# Remote.net
KiCad netlist of a schematic drawn in EAGLE
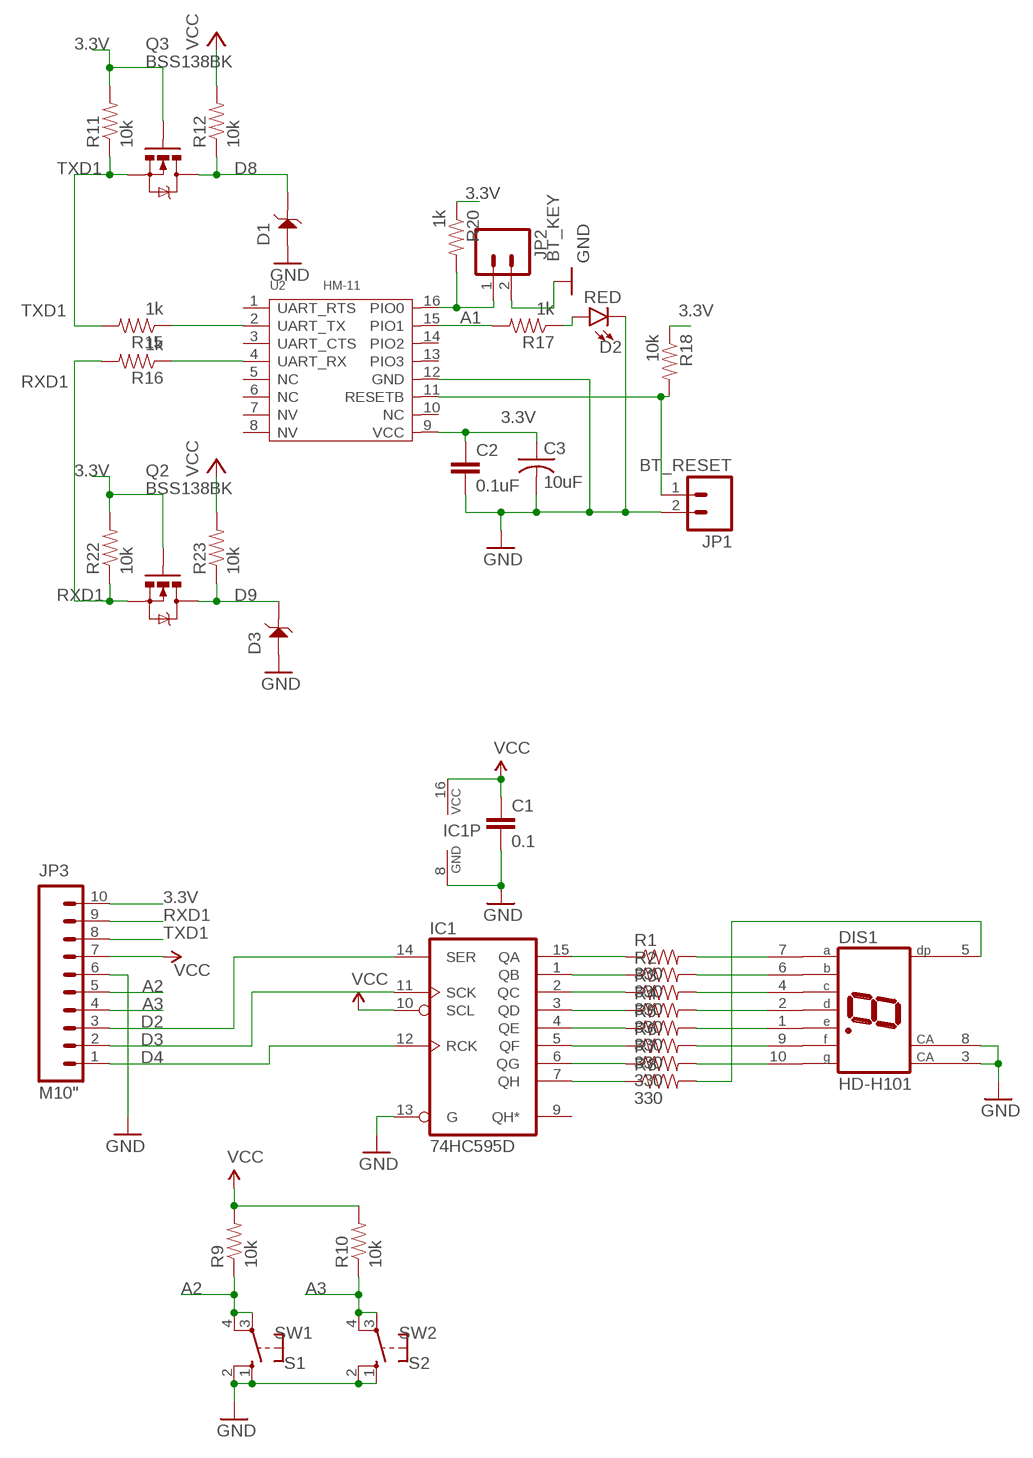
[diagram p0: schematic, sheet 1]

(export (version "E")
  (design (tool "Eeschema 10.0.6"))
  (components
    (comp (ref "C1")
      (value "0.1")
      (footprint "eagle-import:0805")
      (libsource (lib "eagle-import") (part "CAP0805"))
    )
    (comp (ref "C2")
      (value "0.1uF")
      (footprint "eagle-import:0805")
      (libsource (lib "eagle-import") (part "SparkFun-Capacitors_CAP0805"))
    )
    (comp (ref "C3")
      (value "10uF")
      (footprint "eagle-import:C1206")
      (libsource (lib "eagle-import") (part "C-USC1206"))
    )
    (comp (ref "D1")
      (value "SMF5.0A")
      (footprint "eagle-import:SOD123-2.7X1.6")
      (libsource (lib "eagle-import") (part "D-ESD-2P'CESD5V0D1'"))
    )
    (comp (ref "D2")
      (value "RED")
      (footprint "eagle-import:LED-0603")
      (libsource (lib "eagle-import") (part "LED-RED0603"))
    )
    (comp (ref "D3")
      (value "SMF5.0A")
      (footprint "eagle-import:SOD123-2.7X1.6")
      (libsource (lib "eagle-import") (part "D-ESD-2P'CESD5V0D1'"))
    )
    (comp (ref "DIS1")
      (value "HD-H101")
      (footprint "eagle-import:HDSP-M")
      (libsource (lib "eagle-import") (part "HD-H101"))
    )
    (comp (ref "IC1")
      (value "74HC595D")
      (footprint "eagle-import:SO16")
      (libsource (lib "eagle-import") (part "74595DHC"))
    )
    (comp (ref "JP1")
      (value "BT_RESET")
      (footprint "eagle-import:1X02")
      (libsource (lib "eagle-import") (part "M02PTH"))
    )
    (comp (ref "JP2")
      (value "BT_KEY")
      (footprint "eagle-import:1X02")
      (libsource (lib "eagle-import") (part "M02PTH"))
    )
    (comp (ref "JP3")
      (value "M10\"")
      (footprint "eagle-import:1X10")
      (libsource (lib "eagle-import") (part "M10{dblquote}"))
    )
    (comp (ref "Q2")
      (value "BSS138BK")
      (footprint "eagle-import:SOT23-3")
      (libsource (lib "eagle-import") (part "MOSFET-NCHANNELBSS138"))
    )
    (comp (ref "Q3")
      (value "BSS138BK")
      (footprint "eagle-import:SOT23-3")
      (libsource (lib "eagle-import") (part "MOSFET-NCHANNELBSS138"))
    )
    (comp (ref "R1")
      (value "330")
      (footprint "eagle-import:0805")
      (libsource (lib "eagle-import") (part "RESISTOR0805-RES"))
    )
    (comp (ref "R2")
      (value "330")
      (footprint "eagle-import:0805")
      (libsource (lib "eagle-import") (part "RESISTOR0805-RES"))
    )
    (comp (ref "R3")
      (value "330")
      (footprint "eagle-import:0805")
      (libsource (lib "eagle-import") (part "RESISTOR0805-RES"))
    )
    (comp (ref "R4")
      (value "330")
      (footprint "eagle-import:0805")
      (libsource (lib "eagle-import") (part "RESISTOR0805-RES"))
    )
    (comp (ref "R5")
      (value "330")
      (footprint "eagle-import:0805")
      (libsource (lib "eagle-import") (part "RESISTOR0805-RES"))
    )
    (comp (ref "R6")
      (value "330")
      (footprint "eagle-import:0805")
      (libsource (lib "eagle-import") (part "RESISTOR0805-RES"))
    )
    (comp (ref "R7")
      (value "330")
      (footprint "eagle-import:0805")
      (libsource (lib "eagle-import") (part "RESISTOR0805-RES"))
    )
    (comp (ref "R8")
      (value "330")
      (footprint "eagle-import:0805")
      (libsource (lib "eagle-import") (part "RESISTOR0805-RES"))
    )
    (comp (ref "R9")
      (value "10k")
      (footprint "eagle-import:0805")
      (libsource (lib "eagle-import") (part "RESISTOR0805-RES"))
    )
    (comp (ref "R10")
      (value "10k")
      (footprint "eagle-import:0805")
      (libsource (lib "eagle-import") (part "RESISTOR0805-RES"))
    )
    (comp (ref "R11")
      (value "10k")
      (footprint "eagle-import:0805")
      (libsource (lib "eagle-import") (part "RESISTOR0805-RES"))
    )
    (comp (ref "R12")
      (value "10k")
      (footprint "eagle-import:0805")
      (libsource (lib "eagle-import") (part "RESISTOR0805-RES"))
    )
    (comp (ref "R15")
      (value "1k")
      (footprint "eagle-import:0805")
      (libsource (lib "eagle-import") (part "RESISTOR0805-RES"))
    )
    (comp (ref "R16")
      (value "1k")
      (footprint "eagle-import:0805")
      (libsource (lib "eagle-import") (part "RESISTOR0805-RES"))
    )
    (comp (ref "R17")
      (value "1k")
      (footprint "eagle-import:0805")
      (libsource (lib "eagle-import") (part "RESISTOR0805-RES"))
    )
    (comp (ref "R18")
      (value "10k")
      (footprint "eagle-import:0805")
      (libsource (lib "eagle-import") (part "RESISTOR0805-RES"))
    )
    (comp (ref "R20")
      (value "1k")
      (footprint "eagle-import:0805")
      (libsource (lib "eagle-import") (part "RESISTOR0805-RES"))
    )
    (comp (ref "R22")
      (value "10k")
      (footprint "eagle-import:0805")
      (libsource (lib "eagle-import") (part "RESISTOR0805-RES"))
    )
    (comp (ref "R23")
      (value "10k")
      (footprint "eagle-import:0805")
      (libsource (lib "eagle-import") (part "RESISTOR0805-RES"))
    )
    (comp (ref "S1")
      (value "SW1")
      (footprint "eagle-import:B3F-10XX")
      (fields
        (field (name "MPN") "B3F-1000")
        (field (name "MPN_1") "B3F-1000")
        (field (name "OC_FARNELL") "176432")
        (field (name "OC_NEWARK") "36M3542")
      )
      (libsource (lib "eagle-import") (part "10-XX"))
    )
    (comp (ref "S2")
      (value "SW2")
      (footprint "eagle-import:B3F-10XX")
      (fields
        (field (name "MPN") "B3F-1000")
        (field (name "MPN_1") "B3F-1000")
        (field (name "OC_FARNELL") "176432")
        (field (name "OC_NEWARK") "36M3542")
      )
      (libsource (lib "eagle-import") (part "10-XX"))
    )
    (comp (ref "U2")
      (value "HM-11")
      (footprint "eagle-import:16P-18.5X13.5X0.8")
      (libsource (lib "eagle-import") (part "HM-11"))
    )
  )
  (nets
    (net (code "1") (name "/3.3V") (class "Default")
      (node (ref "C2") (pin "1") (pinfunction "1_1") (pintype "passive"))
      (node (ref "C3") (pin "1") (pinfunction "1_1") (pintype "passive"))
      (node (ref "JP3") (pin "10") (pinfunction "10_10") (pintype "passive"))
      (node (ref "Q2") (pin "1") (pinfunction "G_1") (pintype "passive"))
      (node (ref "Q3") (pin "1") (pinfunction "G_1") (pintype "passive"))
      (node (ref "R11") (pin "2") (pinfunction "2_2") (pintype "passive"))
      (node (ref "R18") (pin "1") (pinfunction "1_1") (pintype "passive"))
      (node (ref "R20") (pin "1") (pinfunction "1_1") (pintype "passive"))
      (node (ref "R22") (pin "2") (pinfunction "2_2") (pintype "passive"))
      (node (ref "U2") (pin "9") (pinfunction "VCC_9") (pintype "bidirectional"))
    )
    (net (code "2") (name "/A1") (class "Default")
      (node (ref "R17") (pin "2") (pinfunction "2_2") (pintype "passive"))
      (node (ref "U2") (pin "15") (pinfunction "PIO1_15") (pintype "bidirectional"))
    )
    (net (code "3") (name "/A2") (class "Default")
      (node (ref "JP3") (pin "5") (pinfunction "5_5") (pintype "passive"))
      (node (ref "R9") (pin "1") (pinfunction "1_1") (pintype "passive"))
      (node (ref "S1") (pin "3") (pinfunction "P_3") (pintype "passive"))
      (node (ref "S1") (pin "4") (pinfunction "P1_4") (pintype "passive"))
    )
    (net (code "4") (name "/A3") (class "Default")
      (node (ref "JP3") (pin "4") (pinfunction "4_4") (pintype "passive"))
      (node (ref "R10") (pin "1") (pinfunction "1_1") (pintype "passive"))
      (node (ref "S2") (pin "3") (pinfunction "P_3") (pintype "passive"))
      (node (ref "S2") (pin "4") (pinfunction "P1_4") (pintype "passive"))
    )
    (net (code "5") (name "/D2") (class "Default")
      (node (ref "IC1") (pin "14") (pinfunction "SER_14") (pintype "input"))
      (node (ref "JP3") (pin "3") (pinfunction "3_3") (pintype "passive"))
    )
    (net (code "6") (name "/D3") (class "Default")
      (node (ref "IC1") (pin "11") (pinfunction "SCK_11") (pintype "input"))
      (node (ref "JP3") (pin "2") (pinfunction "2_2") (pintype "passive"))
    )
    (net (code "7") (name "/D4") (class "Default")
      (node (ref "IC1") (pin "12") (pinfunction "RCK_12") (pintype "input"))
      (node (ref "JP3") (pin "1") (pinfunction "1_1") (pintype "passive"))
    )
    (net (code "8") (name "/D8") (class "Default")
      (node (ref "D1") (pin "2") (pinfunction "2_2") (pintype "bidirectional"))
      (node (ref "Q3") (pin "3") (pinfunction "D_3") (pintype "passive"))
      (node (ref "R12") (pin "1") (pinfunction "1_1") (pintype "passive"))
    )
    (net (code "9") (name "/D9") (class "Default")
      (node (ref "D3") (pin "2") (pinfunction "2_2") (pintype "bidirectional"))
      (node (ref "Q2") (pin "3") (pinfunction "D_3") (pintype "passive"))
      (node (ref "R23") (pin "1") (pinfunction "1_1") (pintype "passive"))
    )
    (net (code "10") (name "/RXD1") (class "Default")
      (node (ref "JP3") (pin "9") (pinfunction "9_9") (pintype "passive"))
      (node (ref "Q2") (pin "2") (pinfunction "S_2") (pintype "passive"))
      (node (ref "R16") (pin "2") (pinfunction "2_2") (pintype "passive"))
      (node (ref "R22") (pin "1") (pinfunction "1_1") (pintype "passive"))
    )
    (net (code "11") (name "/TXD1") (class "Default")
      (node (ref "JP3") (pin "8") (pinfunction "8_8") (pintype "passive"))
      (node (ref "Q3") (pin "2") (pinfunction "S_2") (pintype "passive"))
      (node (ref "R11") (pin "1") (pinfunction "1_1") (pintype "passive"))
      (node (ref "R15") (pin "2") (pinfunction "2_2") (pintype "passive"))
    )
    (net (code "12") (name "GND") (class "Default")
      (node (ref "C1") (pin "2") (pinfunction "2_2") (pintype "passive"))
      (node (ref "C2") (pin "2") (pinfunction "2_2") (pintype "passive"))
      (node (ref "C3") (pin "2") (pinfunction "2_2") (pintype "passive"))
      (node (ref "D1") (pin "1") (pinfunction "1_1") (pintype "bidirectional"))
      (node (ref "D2") (pin "C") (pinfunction "C_C") (pintype "passive"))
      (node (ref "D3") (pin "1") (pinfunction "1_1") (pintype "bidirectional"))
      (node (ref "DIS1") (pin "3") (pinfunction "CA_3") (pintype "passive"))
      (node (ref "DIS1") (pin "8") (pinfunction "CA_8") (pintype "passive"))
      (node (ref "IC1") (pin "13") (pinfunction "G_13") (pintype "input"))
      (node (ref "IC1") (pin "8") (pinfunction "GND_8") (pintype "power_in"))
      (node (ref "JP1") (pin "2") (pinfunction "2_2") (pintype "passive"))
      (node (ref "JP2") (pin "2") (pinfunction "2_2") (pintype "passive"))
      (node (ref "JP3") (pin "6") (pinfunction "6_6") (pintype "passive"))
      (node (ref "S1") (pin "1") (pinfunction "S_1") (pintype "passive"))
      (node (ref "S1") (pin "2") (pinfunction "S1_2") (pintype "passive"))
      (node (ref "S2") (pin "1") (pinfunction "S_1") (pintype "passive"))
      (node (ref "S2") (pin "2") (pinfunction "S1_2") (pintype "passive"))
      (node (ref "U2") (pin "12") (pinfunction "GND_12") (pintype "bidirectional"))
    )
    (net (code "13") (name "Net-(D2-PadA)") (class "Default")
      (node (ref "D2") (pin "A") (pinfunction "A_A") (pintype "passive"))
      (node (ref "R17") (pin "1") (pinfunction "1_1") (pintype "passive"))
    )
    (net (code "14") (name "Net-(DIS1-A)") (class "Default")
      (node (ref "DIS1") (pin "7") (pinfunction "A_7") (pintype "passive"))
      (node (ref "R1") (pin "2") (pinfunction "2_2") (pintype "passive"))
    )
    (net (code "15") (name "Net-(DIS1-B)") (class "Default")
      (node (ref "DIS1") (pin "6") (pinfunction "B_6") (pintype "passive"))
      (node (ref "R2") (pin "2") (pinfunction "2_2") (pintype "passive"))
    )
    (net (code "16") (name "Net-(DIS1-C)") (class "Default")
      (node (ref "DIS1") (pin "4") (pinfunction "C_4") (pintype "passive"))
      (node (ref "R3") (pin "2") (pinfunction "2_2") (pintype "passive"))
    )
    (net (code "17") (name "Net-(DIS1-D)") (class "Default")
      (node (ref "DIS1") (pin "2") (pinfunction "D_2") (pintype "passive"))
      (node (ref "R4") (pin "2") (pinfunction "2_2") (pintype "passive"))
    )
    (net (code "18") (name "Net-(DIS1-DP)") (class "Default")
      (node (ref "DIS1") (pin "5") (pinfunction "DP_5") (pintype "passive"))
      (node (ref "R8") (pin "2") (pinfunction "2_2") (pintype "passive"))
    )
    (net (code "19") (name "Net-(DIS1-E)") (class "Default")
      (node (ref "DIS1") (pin "1") (pinfunction "E_1") (pintype "passive"))
      (node (ref "R5") (pin "2") (pinfunction "2_2") (pintype "passive"))
    )
    (net (code "20") (name "Net-(DIS1-F)") (class "Default")
      (node (ref "DIS1") (pin "9") (pinfunction "F_9") (pintype "passive"))
      (node (ref "R6") (pin "2") (pinfunction "2_2") (pintype "passive"))
    )
    (net (code "21") (name "Net-(DIS1-G)") (class "Default")
      (node (ref "DIS1") (pin "10") (pinfunction "G_10") (pintype "passive"))
      (node (ref "R7") (pin "2") (pinfunction "2_2") (pintype "passive"))
    )
    (net (code "22") (name "Net-(IC1A-QA)") (class "Default")
      (node (ref "IC1") (pin "15") (pinfunction "QA_15") (pintype "tri_state"))
      (node (ref "R1") (pin "1") (pinfunction "1_1") (pintype "passive"))
    )
    (net (code "23") (name "Net-(IC1A-QB)") (class "Default")
      (node (ref "IC1") (pin "1") (pinfunction "QB_1") (pintype "tri_state"))
      (node (ref "R2") (pin "1") (pinfunction "1_1") (pintype "passive"))
    )
    (net (code "24") (name "Net-(IC1A-QC)") (class "Default")
      (node (ref "IC1") (pin "2") (pinfunction "QC_2") (pintype "tri_state"))
      (node (ref "R3") (pin "1") (pinfunction "1_1") (pintype "passive"))
    )
    (net (code "25") (name "Net-(IC1A-QD)") (class "Default")
      (node (ref "IC1") (pin "3") (pinfunction "QD_3") (pintype "tri_state"))
      (node (ref "R4") (pin "1") (pinfunction "1_1") (pintype "passive"))
    )
    (net (code "26") (name "Net-(IC1A-QE)") (class "Default")
      (node (ref "IC1") (pin "4") (pinfunction "QE_4") (pintype "tri_state"))
      (node (ref "R5") (pin "1") (pinfunction "1_1") (pintype "passive"))
    )
    (net (code "27") (name "Net-(IC1A-QF)") (class "Default")
      (node (ref "IC1") (pin "5") (pinfunction "QF_5") (pintype "tri_state"))
      (node (ref "R6") (pin "1") (pinfunction "1_1") (pintype "passive"))
    )
    (net (code "28") (name "Net-(IC1A-QG)") (class "Default")
      (node (ref "IC1") (pin "6") (pinfunction "QG_6") (pintype "tri_state"))
      (node (ref "R7") (pin "1") (pinfunction "1_1") (pintype "passive"))
    )
    (net (code "29") (name "Net-(IC1A-QH)") (class "Default")
      (node (ref "IC1") (pin "7") (pinfunction "QH_7") (pintype "tri_state"))
      (node (ref "R8") (pin "1") (pinfunction "1_1") (pintype "passive"))
    )
    (net (code "30") (name "Net-(U2-PIO0)") (class "Default")
      (node (ref "JP2") (pin "1") (pinfunction "1_1") (pintype "passive"))
      (node (ref "R20") (pin "2") (pinfunction "2_2") (pintype "passive"))
      (node (ref "U2") (pin "16") (pinfunction "PIO0_16") (pintype "bidirectional"))
    )
    (net (code "31") (name "Net-(U2-RESETB)") (class "Default")
      (node (ref "JP1") (pin "1") (pinfunction "1_1") (pintype "passive"))
      (node (ref "R18") (pin "2") (pinfunction "2_2") (pintype "passive"))
      (node (ref "U2") (pin "11") (pinfunction "RESETB_11") (pintype "bidirectional"))
    )
    (net (code "32") (name "Net-(U2-UART_RX)") (class "Default")
      (node (ref "R16") (pin "1") (pinfunction "1_1") (pintype "passive"))
      (node (ref "U2") (pin "4") (pinfunction "UART_RX_4") (pintype "bidirectional"))
    )
    (net (code "33") (name "Net-(U2-UART_TX)") (class "Default")
      (node (ref "R15") (pin "1") (pinfunction "1_1") (pintype "passive"))
      (node (ref "U2") (pin "2") (pinfunction "UART_TX_2") (pintype "bidirectional"))
    )
    (net (code "34") (name "VCC") (class "Default")
      (node (ref "C1") (pin "1") (pinfunction "1_1") (pintype "passive"))
      (node (ref "IC1") (pin "10") (pinfunction "SCL_10") (pintype "input"))
      (node (ref "IC1") (pin "16") (pinfunction "VCC_16") (pintype "power_in"))
      (node (ref "JP3") (pin "7") (pinfunction "7_7") (pintype "passive"))
      (node (ref "R10") (pin "2") (pinfunction "2_2") (pintype "passive"))
      (node (ref "R12") (pin "2") (pinfunction "2_2") (pintype "passive"))
      (node (ref "R23") (pin "2") (pinfunction "2_2") (pintype "passive"))
      (node (ref "R9") (pin "2") (pinfunction "2_2") (pintype "passive"))
    )
    (net (code "35") (name "unconnected-(IC1A-QH*-Pad9)") (class "Default")
      (node (ref "IC1") (pin "9") (pinfunction "QH*_9") (pintype "tri_state"))
    )
    (net (code "36") (name "unconnected-(U2-NC-Pad5)") (class "Default")
      (node (ref "U2") (pin "5") (pinfunction "NC_5") (pintype "bidirectional"))
    )
    (net (code "37") (name "unconnected-(U2-NC-Pad6)") (class "Default")
      (node (ref "U2") (pin "6") (pinfunction "NC_6") (pintype "bidirectional"))
    )
    (net (code "38") (name "unconnected-(U2-NC-Pad10)") (class "Default")
      (node (ref "U2") (pin "10") (pinfunction "NC_10") (pintype "bidirectional"))
    )
    (net (code "39") (name "unconnected-(U2-NV-Pad7)") (class "Default")
      (node (ref "U2") (pin "7") (pinfunction "NV_7") (pintype "bidirectional"))
    )
    (net (code "40") (name "unconnected-(U2-NV-Pad8)") (class "Default")
      (node (ref "U2") (pin "8") (pinfunction "NV_8") (pintype "bidirectional"))
    )
    (net (code "41") (name "unconnected-(U2-PIO2-Pad14)") (class "Default")
      (node (ref "U2") (pin "14") (pinfunction "PIO2_14") (pintype "bidirectional"))
    )
    (net (code "42") (name "unconnected-(U2-PIO3-Pad13)") (class "Default")
      (node (ref "U2") (pin "13") (pinfunction "PIO3_13") (pintype "bidirectional"))
    )
    (net (code "43") (name "unconnected-(U2-UART_CTS-Pad3)") (class "Default")
      (node (ref "U2") (pin "3") (pinfunction "UART_CTS_3") (pintype "bidirectional"))
    )
    (net (code "44") (name "unconnected-(U2-UART_RTS-Pad1)") (class "Default")
      (node (ref "U2") (pin "1") (pinfunction "UART_RTS_1") (pintype "bidirectional"))
    )
  )
)
